# sheet_1_final.net
KiCad netlist of a schematic drawn in Altium Designer
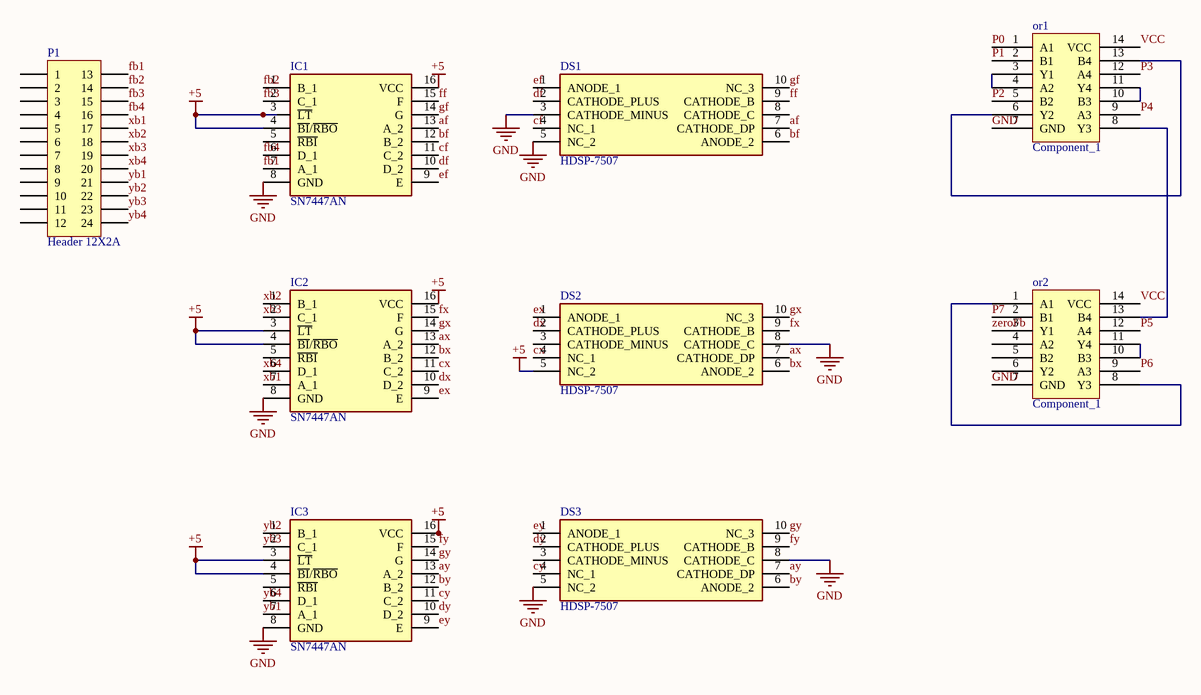
[diagram p0: sheet 1 final.SchDoc]

(export (version "E")
  (design (tool "Eeschema 10.0.6"))
  (components
    (comp (ref "DS1")
      (value "HDSP-7507")
      (footprint "SamacSys:DIPS508W51P254L1270H609Q10N")
      (description "Display")
      (fields (field (name "MOUSER PART NUMBER") "630-HDSP-7507"))
      (libsource (lib "*") (part "HDSP-7507"))
    )
    (comp (ref "DS2")
      (value "HDSP-7507")
      (footprint "SamacSys:DIPS508W51P254L1270H609Q10N")
      (description "Display")
      (fields (field (name "MOUSER PART NUMBER") "630-HDSP-7507"))
      (libsource (lib "*") (part "HDSP-7507"))
    )
    (comp (ref "DS3")
      (value "HDSP-7507")
      (footprint "SamacSys:DIPS508W51P254L1270H609Q10N")
      (description "Display")
      (fields (field (name "MOUSER PART NUMBER") "630-HDSP-7507"))
      (libsource (lib "*") (part "HDSP-7507"))
    )
    (comp (ref "IC1")
      (value "SN7447AN")
      (footprint "SamacSys:DIP762W66P254L2134H508Q16N")
      (description "Integrated Circuit")
      (fields (field (name "MOUSER PART NUMBER") "595-SN7447AN") (field (name "RS PART NUMBER") "0305406P"))
      (libsource (lib "*") (part "SN7447AN"))
    )
    (comp (ref "IC2")
      (value "SN7447AN")
      (footprint "SamacSys:DIP762W66P254L2134H508Q16N")
      (description "Integrated Circuit")
      (fields (field (name "MOUSER PART NUMBER") "595-SN7447AN") (field (name "RS PART NUMBER") "0305406P"))
      (libsource (lib "*") (part "SN7447AN"))
    )
    (comp (ref "IC3")
      (value "SN7447AN")
      (footprint "SamacSys:DIP762W66P254L2134H508Q16N")
      (description "Integrated Circuit")
      (fields (field (name "MOUSER PART NUMBER") "595-SN7447AN") (field (name "RS PART NUMBER") "0305406P"))
      (libsource (lib "*") (part "SN7447AN"))
    )
    (comp (ref "or1")
      (value "Component_1")
      (footprint "and gate:PCBComponent_1")
      (libsource (lib "and schemetic") (part "Component_1"))
    )
    (comp (ref "or2")
      (value "Component_1")
      (footprint "and gate:PCBComponent_1")
      (libsource (lib "and schemetic") (part "Component_1"))
    )
    (comp (ref "P1")
      (value "Header 12X2A")
      (footprint "HDR2X12_CEN")
      (description "Header, 12-Pin, Dual row")
      (fields (field (name "PUBLISHER") "Altium Limited"))
      (libsource (lib "Miscellaneous Connectors") (part "Header 12X2A"))
    )
  )
  (nets
    (net (code "1") (name "+5") (class "Default")
      (node (ref "DS2") (pin "5") (pinfunction "NC_2_5") (pintype "passive"))
      (node (ref "IC1") (pin "16") (pinfunction "VCC_16") (pintype "passive"))
      (node (ref "IC1") (pin "3") (pinfunction "~{LT}_3") (pintype "passive"))
      (node (ref "IC1") (pin "4") (pinfunction "~{BI}/~{RBO}_4") (pintype "passive"))
      (node (ref "IC2") (pin "16") (pinfunction "VCC_16") (pintype "passive"))
      (node (ref "IC2") (pin "3") (pinfunction "~{LT}_3") (pintype "passive"))
      (node (ref "IC2") (pin "4") (pinfunction "~{BI}/~{RBO}_4") (pintype "passive"))
      (node (ref "IC3") (pin "16") (pinfunction "VCC_16") (pintype "passive"))
      (node (ref "IC3") (pin "3") (pinfunction "~{LT}_3") (pintype "passive"))
      (node (ref "IC3") (pin "4") (pinfunction "~{BI}/~{RBO}_4") (pintype "passive"))
    )
    (net (code "2") (name "/P0") (class "Default")
      (node (ref "or1") (pin "1") (pinfunction "A1_1") (pintype "passive"))
    )
    (net (code "3") (name "/P1") (class "Default")
      (node (ref "or1") (pin "2") (pinfunction "B1_2") (pintype "passive"))
    )
    (net (code "4") (name "/P2") (class "Default")
      (node (ref "or1") (pin "5") (pinfunction "B2_5") (pintype "passive"))
    )
    (net (code "5") (name "/P3") (class "Default")
      (node (ref "or1") (pin "12") (pinfunction "A4_12") (pintype "passive"))
    )
    (net (code "6") (name "/P4") (class "Default")
      (node (ref "or1") (pin "9") (pinfunction "A3_9") (pintype "passive"))
    )
    (net (code "7") (name "/P5") (class "Default")
      (node (ref "or2") (pin "12") (pinfunction "A4_12") (pintype "passive"))
    )
    (net (code "8") (name "/P6") (class "Default")
      (node (ref "or2") (pin "9") (pinfunction "A3_9") (pintype "passive"))
    )
    (net (code "9") (name "/P7") (class "Default")
      (node (ref "or2") (pin "2") (pinfunction "B1_2") (pintype "passive"))
    )
    (net (code "10") (name "/VCC") (class "Default")
      (node (ref "or1") (pin "14") (pinfunction "VCC_14") (pintype "passive"))
      (node (ref "or2") (pin "14") (pinfunction "VCC_14") (pintype "passive"))
    )
    (net (code "11") (name "/af") (class "Default")
      (node (ref "DS1") (pin "7") (pinfunction "CATHODE_DP_7") (pintype "passive"))
      (node (ref "IC1") (pin "13") (pinfunction "A_2_13") (pintype "passive"))
    )
    (net (code "12") (name "/ax") (class "Default")
      (node (ref "DS2") (pin "7") (pinfunction "CATHODE_DP_7") (pintype "passive"))
      (node (ref "IC2") (pin "13") (pinfunction "A_2_13") (pintype "passive"))
    )
    (net (code "13") (name "/ay") (class "Default")
      (node (ref "DS3") (pin "7") (pinfunction "CATHODE_DP_7") (pintype "passive"))
      (node (ref "IC3") (pin "13") (pinfunction "A_2_13") (pintype "passive"))
    )
    (net (code "14") (name "/bf") (class "Default")
      (node (ref "DS1") (pin "6") (pinfunction "ANODE_2_6") (pintype "passive"))
      (node (ref "IC1") (pin "12") (pinfunction "B_2_12") (pintype "passive"))
    )
    (net (code "15") (name "/bx") (class "Default")
      (node (ref "DS2") (pin "6") (pinfunction "ANODE_2_6") (pintype "passive"))
      (node (ref "IC2") (pin "12") (pinfunction "B_2_12") (pintype "passive"))
    )
    (net (code "16") (name "/by") (class "Default")
      (node (ref "DS3") (pin "6") (pinfunction "ANODE_2_6") (pintype "passive"))
      (node (ref "IC3") (pin "12") (pinfunction "B_2_12") (pintype "passive"))
    )
    (net (code "17") (name "/cf") (class "Default")
      (node (ref "DS1") (pin "4") (pinfunction "NC_1_4") (pintype "passive"))
      (node (ref "IC1") (pin "11") (pinfunction "C_2_11") (pintype "passive"))
    )
    (net (code "18") (name "/cx") (class "Default")
      (node (ref "DS2") (pin "4") (pinfunction "NC_1_4") (pintype "passive"))
      (node (ref "IC2") (pin "11") (pinfunction "C_2_11") (pintype "passive"))
    )
    (net (code "19") (name "/cy") (class "Default")
      (node (ref "DS3") (pin "4") (pinfunction "NC_1_4") (pintype "passive"))
      (node (ref "IC3") (pin "11") (pinfunction "C_2_11") (pintype "passive"))
    )
    (net (code "20") (name "/df") (class "Default")
      (node (ref "DS1") (pin "2") (pinfunction "CATHODE_PLUS_2") (pintype "passive"))
      (node (ref "IC1") (pin "10") (pinfunction "D_2_10") (pintype "passive"))
    )
    (net (code "21") (name "/dx") (class "Default")
      (node (ref "DS2") (pin "2") (pinfunction "CATHODE_PLUS_2") (pintype "passive"))
      (node (ref "IC2") (pin "10") (pinfunction "D_2_10") (pintype "passive"))
    )
    (net (code "22") (name "/dy") (class "Default")
      (node (ref "DS3") (pin "2") (pinfunction "CATHODE_PLUS_2") (pintype "passive"))
      (node (ref "IC3") (pin "10") (pinfunction "D_2_10") (pintype "passive"))
    )
    (net (code "23") (name "/ef") (class "Default")
      (node (ref "DS1") (pin "1") (pinfunction "ANODE_1_1") (pintype "passive"))
      (node (ref "IC1") (pin "9") (pinfunction "E_9") (pintype "passive"))
    )
    (net (code "24") (name "/ex") (class "Default")
      (node (ref "DS2") (pin "1") (pinfunction "ANODE_1_1") (pintype "passive"))
      (node (ref "IC2") (pin "9") (pinfunction "E_9") (pintype "passive"))
    )
    (net (code "25") (name "/ey") (class "Default")
      (node (ref "DS3") (pin "1") (pinfunction "ANODE_1_1") (pintype "passive"))
      (node (ref "IC3") (pin "9") (pinfunction "E_9") (pintype "passive"))
    )
    (net (code "26") (name "/fb1") (class "Default")
      (node (ref "IC1") (pin "7") (pinfunction "A_1_7") (pintype "passive"))
      (node (ref "P1") (pin "13") (pinfunction "13_13") (pintype "passive"))
    )
    (net (code "27") (name "/fb2") (class "Default")
      (node (ref "IC1") (pin "1") (pinfunction "B_1_1") (pintype "passive"))
      (node (ref "P1") (pin "14") (pinfunction "14_14") (pintype "passive"))
    )
    (net (code "28") (name "/fb3") (class "Default")
      (node (ref "IC1") (pin "2") (pinfunction "C_1_2") (pintype "passive"))
      (node (ref "P1") (pin "15") (pinfunction "15_15") (pintype "passive"))
    )
    (net (code "29") (name "/fb4") (class "Default")
      (node (ref "IC1") (pin "6") (pinfunction "D_1_6") (pintype "passive"))
      (node (ref "P1") (pin "16") (pinfunction "16_16") (pintype "passive"))
    )
    (net (code "30") (name "/ff") (class "Default")
      (node (ref "DS1") (pin "9") (pinfunction "CATHODE_B_9") (pintype "passive"))
      (node (ref "IC1") (pin "15") (pinfunction "F_15") (pintype "passive"))
    )
    (net (code "31") (name "/fx") (class "Default")
      (node (ref "DS2") (pin "9") (pinfunction "CATHODE_B_9") (pintype "passive"))
      (node (ref "IC2") (pin "15") (pinfunction "F_15") (pintype "passive"))
    )
    (net (code "32") (name "/fy") (class "Default")
      (node (ref "DS3") (pin "9") (pinfunction "CATHODE_B_9") (pintype "passive"))
      (node (ref "IC3") (pin "15") (pinfunction "F_15") (pintype "passive"))
    )
    (net (code "33") (name "/gf") (class "Default")
      (node (ref "DS1") (pin "10") (pinfunction "NC_3_10") (pintype "passive"))
      (node (ref "IC1") (pin "14") (pinfunction "G_14") (pintype "passive"))
    )
    (net (code "34") (name "/gx") (class "Default")
      (node (ref "DS2") (pin "10") (pinfunction "NC_3_10") (pintype "passive"))
      (node (ref "IC2") (pin "14") (pinfunction "G_14") (pintype "passive"))
    )
    (net (code "35") (name "/gy") (class "Default")
      (node (ref "DS3") (pin "10") (pinfunction "NC_3_10") (pintype "passive"))
      (node (ref "IC3") (pin "14") (pinfunction "G_14") (pintype "passive"))
    )
    (net (code "36") (name "/xb1") (class "Default")
      (node (ref "IC2") (pin "7") (pinfunction "A_1_7") (pintype "passive"))
      (node (ref "P1") (pin "17") (pinfunction "17_17") (pintype "passive"))
    )
    (net (code "37") (name "/xb2") (class "Default")
      (node (ref "IC2") (pin "1") (pinfunction "B_1_1") (pintype "passive"))
      (node (ref "P1") (pin "18") (pinfunction "18_18") (pintype "passive"))
    )
    (net (code "38") (name "/xb3") (class "Default")
      (node (ref "IC2") (pin "2") (pinfunction "C_1_2") (pintype "passive"))
      (node (ref "P1") (pin "19") (pinfunction "19_19") (pintype "passive"))
    )
    (net (code "39") (name "/xb4") (class "Default")
      (node (ref "IC2") (pin "6") (pinfunction "D_1_6") (pintype "passive"))
      (node (ref "P1") (pin "20") (pinfunction "20_20") (pintype "passive"))
    )
    (net (code "40") (name "/yb1") (class "Default")
      (node (ref "IC3") (pin "7") (pinfunction "A_1_7") (pintype "passive"))
      (node (ref "P1") (pin "21") (pinfunction "21_21") (pintype "passive"))
    )
    (net (code "41") (name "/yb2") (class "Default")
      (node (ref "IC3") (pin "1") (pinfunction "B_1_1") (pintype "passive"))
      (node (ref "P1") (pin "22") (pinfunction "22_22") (pintype "passive"))
    )
    (net (code "42") (name "/yb3") (class "Default")
      (node (ref "IC3") (pin "2") (pinfunction "C_1_2") (pintype "passive"))
      (node (ref "P1") (pin "23") (pinfunction "23_23") (pintype "passive"))
    )
    (net (code "43") (name "/yb4") (class "Default")
      (node (ref "IC3") (pin "6") (pinfunction "D_1_6") (pintype "passive"))
      (node (ref "P1") (pin "24") (pinfunction "24_24") (pintype "passive"))
    )
    (net (code "44") (name "/zeroFb") (class "Default")
      (node (ref "or2") (pin "3") (pinfunction "Y1_3") (pintype "passive"))
    )
    (net (code "45") (name "GND") (class "Default")
      (node (ref "DS1") (pin "3") (pinfunction "CATHODE_MINUS_3") (pintype "passive"))
      (node (ref "DS1") (pin "5") (pinfunction "NC_2_5") (pintype "passive"))
      (node (ref "DS2") (pin "8") (pinfunction "CATHODE_C_8") (pintype "passive"))
      (node (ref "DS3") (pin "5") (pinfunction "NC_2_5") (pintype "passive"))
      (node (ref "DS3") (pin "8") (pinfunction "CATHODE_C_8") (pintype "passive"))
      (node (ref "IC1") (pin "8") (pinfunction "GND_8") (pintype "passive"))
      (node (ref "IC2") (pin "8") (pinfunction "GND_8") (pintype "passive"))
      (node (ref "IC3") (pin "8") (pinfunction "GND_8") (pintype "passive"))
      (node (ref "or1") (pin "7") (pinfunction "GND_7") (pintype "passive"))
      (node (ref "or2") (pin "7") (pinfunction "GND_7") (pintype "passive"))
    )
    (net (code "46") (name "Net-(or1-A2)") (class "Default")
      (node (ref "or1") (pin "3") (pinfunction "Y1_3") (pintype "passive"))
      (node (ref "or1") (pin "4") (pinfunction "A2_4") (pintype "passive"))
    )
    (net (code "47") (name "Net-(or1-B3)") (class "Default")
      (node (ref "or1") (pin "10") (pinfunction "B3_10") (pintype "passive"))
      (node (ref "or1") (pin "11") (pinfunction "Y4_11") (pintype "passive"))
    )
    (net (code "48") (name "Net-(or1-B4)") (class "Default")
      (node (ref "or1") (pin "13") (pinfunction "B4_13") (pintype "passive"))
      (node (ref "or1") (pin "6") (pinfunction "Y2_6") (pintype "passive"))
    )
    (net (code "49") (name "Net-(or1-Y3)") (class "Default")
      (node (ref "or1") (pin "8") (pinfunction "Y3_8") (pintype "passive"))
      (node (ref "or2") (pin "13") (pinfunction "B4_13") (pintype "passive"))
    )
    (net (code "50") (name "Net-(or2-A1)") (class "Default")
      (node (ref "or2") (pin "1") (pinfunction "A1_1") (pintype "passive"))
      (node (ref "or2") (pin "8") (pinfunction "Y3_8") (pintype "passive"))
    )
    (net (code "51") (name "Net-(or2-B3)") (class "Default")
      (node (ref "or2") (pin "10") (pinfunction "B3_10") (pintype "passive"))
      (node (ref "or2") (pin "11") (pinfunction "Y4_11") (pintype "passive"))
    )
    (net (code "52") (name "unconnected-(DS1-CATHODE_C-Pad8)") (class "Default")
      (node (ref "DS1") (pin "8") (pinfunction "CATHODE_C_8") (pintype "passive"))
    )
    (net (code "53") (name "unconnected-(DS2-CATHODE_MINUS-Pad3)") (class "Default")
      (node (ref "DS2") (pin "3") (pinfunction "CATHODE_MINUS_3") (pintype "passive"))
    )
    (net (code "54") (name "unconnected-(DS3-CATHODE_MINUS-Pad3)") (class "Default")
      (node (ref "DS3") (pin "3") (pinfunction "CATHODE_MINUS_3") (pintype "passive"))
    )
    (net (code "55") (name "unconnected-(IC1-~{RBI}-Pad5)") (class "Default")
      (node (ref "IC1") (pin "5") (pinfunction "~{RBI}_5") (pintype "passive"))
    )
    (net (code "56") (name "unconnected-(IC2-~{RBI}-Pad5)") (class "Default")
      (node (ref "IC2") (pin "5") (pinfunction "~{RBI}_5") (pintype "passive"))
    )
    (net (code "57") (name "unconnected-(IC3-~{RBI}-Pad5)") (class "Default")
      (node (ref "IC3") (pin "5") (pinfunction "~{RBI}_5") (pintype "passive"))
    )
    (net (code "58") (name "unconnected-(P1-Pad1)") (class "Default")
      (node (ref "P1") (pin "1") (pinfunction "1_1") (pintype "passive"))
    )
    (net (code "59") (name "unconnected-(P1-Pad2)") (class "Default")
      (node (ref "P1") (pin "2") (pinfunction "2_2") (pintype "passive"))
    )
    (net (code "60") (name "unconnected-(P1-Pad3)") (class "Default")
      (node (ref "P1") (pin "3") (pinfunction "3_3") (pintype "passive"))
    )
    (net (code "61") (name "unconnected-(P1-Pad4)") (class "Default")
      (node (ref "P1") (pin "4") (pinfunction "4_4") (pintype "passive"))
    )
    (net (code "62") (name "unconnected-(P1-Pad5)") (class "Default")
      (node (ref "P1") (pin "5") (pinfunction "5_5") (pintype "passive"))
    )
    (net (code "63") (name "unconnected-(P1-Pad6)") (class "Default")
      (node (ref "P1") (pin "6") (pinfunction "6_6") (pintype "passive"))
    )
    (net (code "64") (name "unconnected-(P1-Pad7)") (class "Default")
      (node (ref "P1") (pin "7") (pinfunction "7_7") (pintype "passive"))
    )
    (net (code "65") (name "unconnected-(P1-Pad8)") (class "Default")
      (node (ref "P1") (pin "8") (pinfunction "8_8") (pintype "passive"))
    )
    (net (code "66") (name "unconnected-(P1-Pad9)") (class "Default")
      (node (ref "P1") (pin "9") (pinfunction "9_9") (pintype "passive"))
    )
    (net (code "67") (name "unconnected-(P1-Pad10)") (class "Default")
      (node (ref "P1") (pin "10") (pinfunction "10_10") (pintype "passive"))
    )
    (net (code "68") (name "unconnected-(P1-Pad11)") (class "Default")
      (node (ref "P1") (pin "11") (pinfunction "11_11") (pintype "passive"))
    )
    (net (code "69") (name "unconnected-(P1-Pad12)") (class "Default")
      (node (ref "P1") (pin "12") (pinfunction "12_12") (pintype "passive"))
    )
    (net (code "70") (name "unconnected-(or2-A2-Pad4)") (class "Default")
      (node (ref "or2") (pin "4") (pinfunction "A2_4") (pintype "passive"))
    )
    (net (code "71") (name "unconnected-(or2-B2-Pad5)") (class "Default")
      (node (ref "or2") (pin "5") (pinfunction "B2_5") (pintype "passive"))
    )
    (net (code "72") (name "unconnected-(or2-Y2-Pad6)") (class "Default")
      (node (ref "or2") (pin "6") (pinfunction "Y2_6") (pintype "passive"))
    )
  )
)
